# bone_capes.net
KiCad netlist of a schematic drawn in Altium Designer
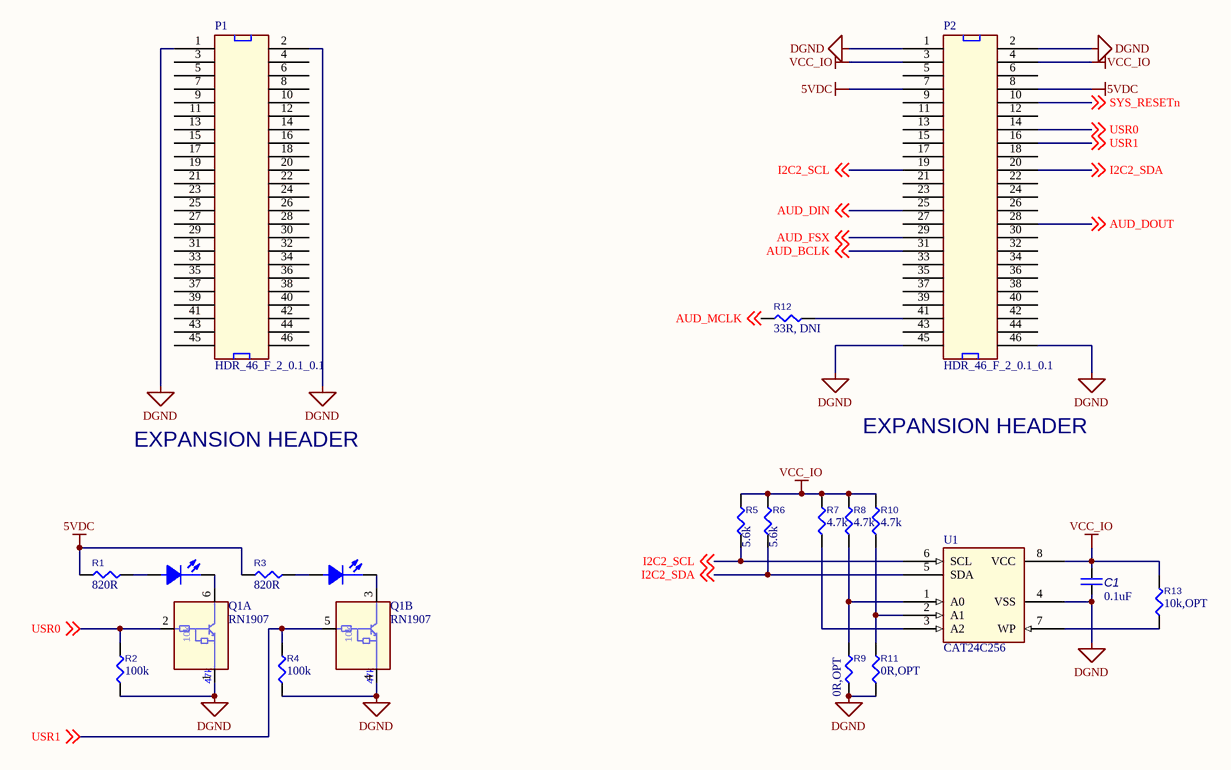
[diagram p0: bone_capes.SchDoc]

(export (version "E")
  (design (tool "Eeschema 10.0.6"))
  (components
    (comp (ref "C1")
      (value "0.1uF")
      (footprint "CC1608-0603")
      (description "C0603")
      (libsource (lib "usomiq-audio") (part "C0603"))
    )
    (comp (ref "D1")
      (value "LED0805")
      (footprint "LED0805")
      (description "LED 0805")
      (libsource (lib "am335x-base") (part "LED0805"))
    )
    (comp (ref "D2")
      (value "LED0805")
      (footprint "LED0805")
      (description "LED 0805")
      (libsource (lib "am335x-base") (part "LED0805"))
    )
    (comp (ref "P1")
      (value "HDR_46_F_2_0.1_0.1")
      (footprint "DIP46")
      (description "NN HEADER FMAL 46PS.1\" DL GOLD")
      (fields (field (name "MFR") "major league electronics"))
      (libsource (lib "usomiq-audio") (part "HDR_46_F_2_0.1_0.1"))
    )
    (comp (ref "P2")
      (value "HDR_46_F_2_0.1_0.1")
      (footprint "DIP46")
      (description "NN HEADER FMAL 46PS.1\" DL GOLD")
      (fields (field (name "MFR") "major league electronics"))
      (libsource (lib "usomiq-audio") (part "HDR_46_F_2_0.1_0.1"))
    )
    (comp (ref "Q1")
      (value "RN1907")
      (footprint "SOT363-6L")
      (description "Transistor Silicon NPN")
      (fields (field (name "MFR") "Panasonic"))
      (libsource (lib "am335x-base") (part "RN1907"))
    )
    (comp (ref "R1")
      (value "820R")
      (footprint "RESC1608X55N")
      (description "R0603")
      (libsource (lib "am335x-base") (part "R0603"))
    )
    (comp (ref "R2")
      (value "100k")
      (footprint "RESC1608X55N")
      (description "R0603")
      (libsource (lib "am335x-base") (part "R0603"))
    )
    (comp (ref "R3")
      (value "820R")
      (footprint "RESC1608X55N")
      (description "R0603")
      (libsource (lib "am335x-base") (part "R0603"))
    )
    (comp (ref "R4")
      (value "100k")
      (footprint "RESC1608X55N")
      (description "R0603")
      (libsource (lib "am335x-base") (part "R0603"))
    )
    (comp (ref "R5")
      (value "5.6k")
      (footprint "RESC1608X55N")
      (description "R0603")
      (libsource (lib "usomiq-audio") (part "R0603"))
    )
    (comp (ref "R6")
      (value "5.6k")
      (footprint "RESC1608X55N")
      (description "R0603")
      (libsource (lib "usomiq-audio") (part "R0603"))
    )
    (comp (ref "R7")
      (value "4.7k")
      (footprint "RESC1608X55N")
      (description "R0603")
      (libsource (lib "usomiq-audio") (part "R0603"))
    )
    (comp (ref "R8")
      (value "4.7k")
      (footprint "RESC1608X55N")
      (description "R0603")
      (libsource (lib "usomiq-audio") (part "R0603"))
    )
    (comp (ref "R9")
      (value "0R,OPT")
      (footprint "RESC1608X55N")
      (description "R0603")
      (libsource (lib "usomiq-audio") (part "R0603"))
    )
    (comp (ref "R10")
      (value "4.7k")
      (footprint "RESC1608X55N")
      (description "R0603")
      (libsource (lib "usomiq-audio") (part "R0603"))
    )
    (comp (ref "R11")
      (value "0R,OPT")
      (footprint "RESC1608X55N")
      (description "R0603")
      (libsource (lib "usomiq-audio") (part "R0603"))
    )
    (comp (ref "R12")
      (value "33R, DNI")
      (footprint "RESC1608X55N")
      (description "R0603")
      (libsource (lib "usomiq-audio") (part "R0603"))
    )
    (comp (ref "R13")
      (value "10k,OPT")
      (footprint "RESC1608X55N")
      (description "R0603")
      (libsource (lib "usomiq-audio") (part "R0603"))
    )
    (comp (ref "U1")
      (value "CAT24C256")
      (footprint "SOIC127P600X173-8L")
      (description "256 kb I2C CMOS Serial  EEPROM")
      (fields (field (name "MANUFACTURER") "ON Semiconductor"))
      (libsource (lib "usomiq-audio") (part "CAT24C256"))
    )
  )
  (nets
    (net (code "1") (name "5VDC") (class "Default")
      (node (ref "P2") (pin "7") (pinfunction "4_7") (pintype "passive"))
      (node (ref "P2") (pin "8") (pinfunction "29_8") (pintype "passive"))
      (node (ref "R1") (pin "2") (pinfunction "2_2") (pintype "passive"))
      (node (ref "R3") (pin "2") (pinfunction "2_2") (pintype "passive"))
    )
    (net (code "2") (name "AUD_BCLK") (class "Default")
      (node (ref "P2") (pin "31") (pinfunction "16_31") (pintype "passive"))
    )
    (net (code "3") (name "AUD_DIN") (class "Default")
      (node (ref "P2") (pin "25") (pinfunction "13_25") (pintype "passive"))
    )
    (net (code "4") (name "AUD_DOUT") (class "Default")
      (node (ref "P2") (pin "28") (pinfunction "39_28") (pintype "passive"))
    )
    (net (code "5") (name "AUD_FSX") (class "Default")
      (node (ref "P2") (pin "29") (pinfunction "15_29") (pintype "passive"))
    )
    (net (code "6") (name "AUD_MCLK") (class "Default")
      (node (ref "R12") (pin "1") (pinfunction "1_1") (pintype "passive"))
    )
    (net (code "7") (name "DGND") (class "Default")
      (node (ref "C1") (pin "2") (pinfunction "2_2") (pintype "passive"))
      (node (ref "P1") (pin "1") (pinfunction "1_1") (pintype "passive"))
      (node (ref "P1") (pin "2") (pinfunction "26_2") (pintype "passive"))
      (node (ref "P2") (pin "1") (pinfunction "1_1") (pintype "passive"))
      (node (ref "P2") (pin "2") (pinfunction "26_2") (pintype "passive"))
      (node (ref "P2") (pin "45") (pinfunction "23_45") (pintype "passive"))
      (node (ref "P2") (pin "46") (pinfunction "48_46") (pintype "passive"))
      (node (ref "Q1") (pin "1") (pinfunction "4_1") (pintype "passive"))
      (node (ref "Q1") (pin "4") (pinfunction "4_4") (pintype "passive"))
      (node (ref "R11") (pin "1") (pinfunction "1_1") (pintype "passive"))
      (node (ref "R2") (pin "1") (pinfunction "1_1") (pintype "passive"))
      (node (ref "R4") (pin "1") (pinfunction "1_1") (pintype "passive"))
      (node (ref "R9") (pin "1") (pinfunction "1_1") (pintype "passive"))
      (node (ref "U1") (pin "4") (pinfunction "VSS_4") (pintype "passive"))
    )
    (net (code "8") (name "I2C2_SCL") (class "Default")
      (node (ref "P2") (pin "19") (pinfunction "10_19") (pintype "passive"))
      (node (ref "R5") (pin "1") (pinfunction "1_1") (pintype "passive"))
      (node (ref "U1") (pin "6") (pinfunction "SCL_6") (pintype "input"))
    )
    (net (code "9") (name "I2C2_SDA") (class "Default")
      (node (ref "P2") (pin "20") (pinfunction "35_20") (pintype "passive"))
      (node (ref "R6") (pin "1") (pinfunction "1_1") (pintype "passive"))
      (node (ref "U1") (pin "5") (pinfunction "SDA_5") (pintype "passive"))
    )
    (net (code "10") (name "Net-(D1-A)") (class "Default")
      (node (ref "D1") (pin "1") (pinfunction "A_1") (pintype "passive"))
      (node (ref "R1") (pin "1") (pinfunction "1_1") (pintype "passive"))
    )
    (net (code "11") (name "Net-(D1-C)") (class "Default")
      (node (ref "D1") (pin "2") (pinfunction "C_2") (pintype "passive"))
      (node (ref "Q1") (pin "6") (pinfunction "3_6") (pintype "passive"))
    )
    (net (code "12") (name "Net-(D2-A)") (class "Default")
      (node (ref "D2") (pin "1") (pinfunction "A_1") (pintype "passive"))
      (node (ref "R3") (pin "1") (pinfunction "1_1") (pintype "passive"))
    )
    (net (code "13") (name "Net-(D2-C)") (class "Default")
      (node (ref "D2") (pin "2") (pinfunction "C_2") (pintype "passive"))
      (node (ref "Q1") (pin "3") (pinfunction "3_3") (pintype "passive"))
    )
    (net (code "14") (name "Net-(P2-21)") (class "Default")
      (node (ref "P2") (pin "41") (pinfunction "21_41") (pintype "passive"))
      (node (ref "R12") (pin "2") (pinfunction "2_2") (pintype "passive"))
    )
    (net (code "15") (name "Net-(U1-A0)") (class "Default")
      (node (ref "R8") (pin "1") (pinfunction "1_1") (pintype "passive"))
      (node (ref "R9") (pin "2") (pinfunction "2_2") (pintype "passive"))
      (node (ref "U1") (pin "1") (pinfunction "A0_1") (pintype "input"))
    )
    (net (code "16") (name "Net-(U1-A1)") (class "Default")
      (node (ref "R10") (pin "1") (pinfunction "1_1") (pintype "passive"))
      (node (ref "R11") (pin "2") (pinfunction "2_2") (pintype "passive"))
      (node (ref "U1") (pin "2") (pinfunction "A1_2") (pintype "input"))
    )
    (net (code "17") (name "Net-(U1-A2)") (class "Default")
      (node (ref "R7") (pin "1") (pinfunction "1_1") (pintype "passive"))
      (node (ref "U1") (pin "3") (pinfunction "A2_3") (pintype "input"))
    )
    (net (code "18") (name "Net-(U1-WP)") (class "Default")
      (node (ref "R13") (pin "1") (pinfunction "1_1") (pintype "passive"))
      (node (ref "U1") (pin "7") (pinfunction "WP_7") (pintype "input"))
    )
    (net (code "19") (name "SYS_RESETn") (class "Default")
      (node (ref "P2") (pin "10") (pinfunction "30_10") (pintype "passive"))
    )
    (net (code "20") (name "USR0") (class "Default")
      (node (ref "P2") (pin "14") (pinfunction "32_14") (pintype "passive"))
      (node (ref "Q1") (pin "2") (pinfunction "5_2") (pintype "passive"))
      (node (ref "R2") (pin "2") (pinfunction "2_2") (pintype "passive"))
    )
    (net (code "21") (name "USR1") (class "Default")
      (node (ref "P2") (pin "16") (pinfunction "33_16") (pintype "passive"))
      (node (ref "Q1") (pin "5") (pinfunction "5_5") (pintype "passive"))
      (node (ref "R4") (pin "2") (pinfunction "2_2") (pintype "passive"))
    )
    (net (code "22") (name "VCC_IO") (class "Default")
      (node (ref "C1") (pin "1") (pinfunction "1_1") (pintype "passive"))
      (node (ref "P2") (pin "3") (pinfunction "2_3") (pintype "passive"))
      (node (ref "P2") (pin "4") (pinfunction "27_4") (pintype "passive"))
      (node (ref "R10") (pin "2") (pinfunction "2_2") (pintype "passive"))
      (node (ref "R13") (pin "2") (pinfunction "2_2") (pintype "passive"))
      (node (ref "R5") (pin "2") (pinfunction "2_2") (pintype "passive"))
      (node (ref "R6") (pin "2") (pinfunction "2_2") (pintype "passive"))
      (node (ref "R7") (pin "2") (pinfunction "2_2") (pintype "passive"))
      (node (ref "R8") (pin "2") (pinfunction "2_2") (pintype "passive"))
      (node (ref "U1") (pin "8") (pinfunction "VCC_8") (pintype "passive"))
    )
    (net (code "23") (name "unconnected-(P1-2-Pad3)") (class "Default")
      (node (ref "P1") (pin "3") (pinfunction "2_3") (pintype "passive"))
    )
    (net (code "24") (name "unconnected-(P1-3-Pad5)") (class "Default")
      (node (ref "P1") (pin "5") (pinfunction "3_5") (pintype "passive"))
    )
    (net (code "25") (name "unconnected-(P1-4-Pad7)") (class "Default")
      (node (ref "P1") (pin "7") (pinfunction "4_7") (pintype "passive"))
    )
    (net (code "26") (name "unconnected-(P1-5-Pad9)") (class "Default")
      (node (ref "P1") (pin "9") (pinfunction "5_9") (pintype "passive"))
    )
    (net (code "27") (name "unconnected-(P1-6-Pad11)") (class "Default")
      (node (ref "P1") (pin "11") (pinfunction "6_11") (pintype "passive"))
    )
    (net (code "28") (name "unconnected-(P1-7-Pad13)") (class "Default")
      (node (ref "P1") (pin "13") (pinfunction "7_13") (pintype "passive"))
    )
    (net (code "29") (name "unconnected-(P1-8-Pad15)") (class "Default")
      (node (ref "P1") (pin "15") (pinfunction "8_15") (pintype "passive"))
    )
    (net (code "30") (name "unconnected-(P1-9-Pad17)") (class "Default")
      (node (ref "P1") (pin "17") (pinfunction "9_17") (pintype "passive"))
    )
    (net (code "31") (name "unconnected-(P1-10-Pad19)") (class "Default")
      (node (ref "P1") (pin "19") (pinfunction "10_19") (pintype "passive"))
    )
    (net (code "32") (name "unconnected-(P1-11-Pad21)") (class "Default")
      (node (ref "P1") (pin "21") (pinfunction "11_21") (pintype "passive"))
    )
    (net (code "33") (name "unconnected-(P1-12-Pad23)") (class "Default")
      (node (ref "P1") (pin "23") (pinfunction "12_23") (pintype "passive"))
    )
    (net (code "34") (name "unconnected-(P1-13-Pad25)") (class "Default")
      (node (ref "P1") (pin "25") (pinfunction "13_25") (pintype "passive"))
    )
    (net (code "35") (name "unconnected-(P1-14-Pad27)") (class "Default")
      (node (ref "P1") (pin "27") (pinfunction "14_27") (pintype "passive"))
    )
    (net (code "36") (name "unconnected-(P1-15-Pad29)") (class "Default")
      (node (ref "P1") (pin "29") (pinfunction "15_29") (pintype "passive"))
    )
    (net (code "37") (name "unconnected-(P1-16-Pad31)") (class "Default")
      (node (ref "P1") (pin "31") (pinfunction "16_31") (pintype "passive"))
    )
    (net (code "38") (name "unconnected-(P1-17-Pad33)") (class "Default")
      (node (ref "P1") (pin "33") (pinfunction "17_33") (pintype "passive"))
    )
    (net (code "39") (name "unconnected-(P1-18-Pad35)") (class "Default")
      (node (ref "P1") (pin "35") (pinfunction "18_35") (pintype "passive"))
    )
    (net (code "40") (name "unconnected-(P1-19-Pad37)") (class "Default")
      (node (ref "P1") (pin "37") (pinfunction "19_37") (pintype "passive"))
    )
    (net (code "41") (name "unconnected-(P1-20-Pad39)") (class "Default")
      (node (ref "P1") (pin "39") (pinfunction "20_39") (pintype "passive"))
    )
    (net (code "42") (name "unconnected-(P1-21-Pad41)") (class "Default")
      (node (ref "P1") (pin "41") (pinfunction "21_41") (pintype "passive"))
    )
    (net (code "43") (name "unconnected-(P1-22-Pad43)") (class "Default")
      (node (ref "P1") (pin "43") (pinfunction "22_43") (pintype "passive"))
    )
    (net (code "44") (name "unconnected-(P1-23-Pad45)") (class "Default")
      (node (ref "P1") (pin "45") (pinfunction "23_45") (pintype "passive"))
    )
    (net (code "45") (name "unconnected-(P1-27-Pad4)") (class "Default")
      (node (ref "P1") (pin "4") (pinfunction "27_4") (pintype "passive"))
    )
    (net (code "46") (name "unconnected-(P1-28-Pad6)") (class "Default")
      (node (ref "P1") (pin "6") (pinfunction "28_6") (pintype "passive"))
    )
    (net (code "47") (name "unconnected-(P1-29-Pad8)") (class "Default")
      (node (ref "P1") (pin "8") (pinfunction "29_8") (pintype "passive"))
    )
    (net (code "48") (name "unconnected-(P1-30-Pad10)") (class "Default")
      (node (ref "P1") (pin "10") (pinfunction "30_10") (pintype "passive"))
    )
    (net (code "49") (name "unconnected-(P1-31-Pad12)") (class "Default")
      (node (ref "P1") (pin "12") (pinfunction "31_12") (pintype "passive"))
    )
    (net (code "50") (name "unconnected-(P1-32-Pad14)") (class "Default")
      (node (ref "P1") (pin "14") (pinfunction "32_14") (pintype "passive"))
    )
    (net (code "51") (name "unconnected-(P1-33-Pad16)") (class "Default")
      (node (ref "P1") (pin "16") (pinfunction "33_16") (pintype "passive"))
    )
    (net (code "52") (name "unconnected-(P1-34-Pad18)") (class "Default")
      (node (ref "P1") (pin "18") (pinfunction "34_18") (pintype "passive"))
    )
    (net (code "53") (name "unconnected-(P1-35-Pad20)") (class "Default")
      (node (ref "P1") (pin "20") (pinfunction "35_20") (pintype "passive"))
    )
    (net (code "54") (name "unconnected-(P1-36-Pad22)") (class "Default")
      (node (ref "P1") (pin "22") (pinfunction "36_22") (pintype "passive"))
    )
    (net (code "55") (name "unconnected-(P1-37-Pad24)") (class "Default")
      (node (ref "P1") (pin "24") (pinfunction "37_24") (pintype "passive"))
    )
    (net (code "56") (name "unconnected-(P1-38-Pad26)") (class "Default")
      (node (ref "P1") (pin "26") (pinfunction "38_26") (pintype "passive"))
    )
    (net (code "57") (name "unconnected-(P1-39-Pad28)") (class "Default")
      (node (ref "P1") (pin "28") (pinfunction "39_28") (pintype "passive"))
    )
    (net (code "58") (name "unconnected-(P1-40-Pad30)") (class "Default")
      (node (ref "P1") (pin "30") (pinfunction "40_30") (pintype "passive"))
    )
    (net (code "59") (name "unconnected-(P1-41-Pad32)") (class "Default")
      (node (ref "P1") (pin "32") (pinfunction "41_32") (pintype "passive"))
    )
    (net (code "60") (name "unconnected-(P1-42-Pad34)") (class "Default")
      (node (ref "P1") (pin "34") (pinfunction "42_34") (pintype "passive"))
    )
    (net (code "61") (name "unconnected-(P1-43-Pad36)") (class "Default")
      (node (ref "P1") (pin "36") (pinfunction "43_36") (pintype "passive"))
    )
    (net (code "62") (name "unconnected-(P1-44-Pad38)") (class "Default")
      (node (ref "P1") (pin "38") (pinfunction "44_38") (pintype "passive"))
    )
    (net (code "63") (name "unconnected-(P1-45-Pad40)") (class "Default")
      (node (ref "P1") (pin "40") (pinfunction "45_40") (pintype "passive"))
    )
    (net (code "64") (name "unconnected-(P1-46-Pad42)") (class "Default")
      (node (ref "P1") (pin "42") (pinfunction "46_42") (pintype "passive"))
    )
    (net (code "65") (name "unconnected-(P1-47-Pad44)") (class "Default")
      (node (ref "P1") (pin "44") (pinfunction "47_44") (pintype "passive"))
    )
    (net (code "66") (name "unconnected-(P1-48-Pad46)") (class "Default")
      (node (ref "P1") (pin "46") (pinfunction "48_46") (pintype "passive"))
    )
    (net (code "67") (name "unconnected-(P2-3-Pad5)") (class "Default")
      (node (ref "P2") (pin "5") (pinfunction "3_5") (pintype "passive"))
    )
    (net (code "68") (name "unconnected-(P2-5-Pad9)") (class "Default")
      (node (ref "P2") (pin "9") (pinfunction "5_9") (pintype "passive"))
    )
    (net (code "69") (name "unconnected-(P2-6-Pad11)") (class "Default")
      (node (ref "P2") (pin "11") (pinfunction "6_11") (pintype "passive"))
    )
    (net (code "70") (name "unconnected-(P2-7-Pad13)") (class "Default")
      (node (ref "P2") (pin "13") (pinfunction "7_13") (pintype "passive"))
    )
    (net (code "71") (name "unconnected-(P2-8-Pad15)") (class "Default")
      (node (ref "P2") (pin "15") (pinfunction "8_15") (pintype "passive"))
    )
    (net (code "72") (name "unconnected-(P2-9-Pad17)") (class "Default")
      (node (ref "P2") (pin "17") (pinfunction "9_17") (pintype "passive"))
    )
    (net (code "73") (name "unconnected-(P2-11-Pad21)") (class "Default")
      (node (ref "P2") (pin "21") (pinfunction "11_21") (pintype "passive"))
    )
    (net (code "74") (name "unconnected-(P2-12-Pad23)") (class "Default")
      (node (ref "P2") (pin "23") (pinfunction "12_23") (pintype "passive"))
    )
    (net (code "75") (name "unconnected-(P2-14-Pad27)") (class "Default")
      (node (ref "P2") (pin "27") (pinfunction "14_27") (pintype "passive"))
    )
    (net (code "76") (name "unconnected-(P2-17-Pad33)") (class "Default")
      (node (ref "P2") (pin "33") (pinfunction "17_33") (pintype "passive"))
    )
    (net (code "77") (name "unconnected-(P2-18-Pad35)") (class "Default")
      (node (ref "P2") (pin "35") (pinfunction "18_35") (pintype "passive"))
    )
    (net (code "78") (name "unconnected-(P2-19-Pad37)") (class "Default")
      (node (ref "P2") (pin "37") (pinfunction "19_37") (pintype "passive"))
    )
    (net (code "79") (name "unconnected-(P2-20-Pad39)") (class "Default")
      (node (ref "P2") (pin "39") (pinfunction "20_39") (pintype "passive"))
    )
    (net (code "80") (name "unconnected-(P2-22-Pad43)") (class "Default")
      (node (ref "P2") (pin "43") (pinfunction "22_43") (pintype "passive"))
    )
    (net (code "81") (name "unconnected-(P2-28-Pad6)") (class "Default")
      (node (ref "P2") (pin "6") (pinfunction "28_6") (pintype "passive"))
    )
    (net (code "82") (name "unconnected-(P2-31-Pad12)") (class "Default")
      (node (ref "P2") (pin "12") (pinfunction "31_12") (pintype "passive"))
    )
    (net (code "83") (name "unconnected-(P2-34-Pad18)") (class "Default")
      (node (ref "P2") (pin "18") (pinfunction "34_18") (pintype "passive"))
    )
    (net (code "84") (name "unconnected-(P2-36-Pad22)") (class "Default")
      (node (ref "P2") (pin "22") (pinfunction "36_22") (pintype "passive"))
    )
    (net (code "85") (name "unconnected-(P2-37-Pad24)") (class "Default")
      (node (ref "P2") (pin "24") (pinfunction "37_24") (pintype "passive"))
    )
    (net (code "86") (name "unconnected-(P2-38-Pad26)") (class "Default")
      (node (ref "P2") (pin "26") (pinfunction "38_26") (pintype "passive"))
    )
    (net (code "87") (name "unconnected-(P2-40-Pad30)") (class "Default")
      (node (ref "P2") (pin "30") (pinfunction "40_30") (pintype "passive"))
    )
    (net (code "88") (name "unconnected-(P2-41-Pad32)") (class "Default")
      (node (ref "P2") (pin "32") (pinfunction "41_32") (pintype "passive"))
    )
    (net (code "89") (name "unconnected-(P2-42-Pad34)") (class "Default")
      (node (ref "P2") (pin "34") (pinfunction "42_34") (pintype "passive"))
    )
    (net (code "90") (name "unconnected-(P2-43-Pad36)") (class "Default")
      (node (ref "P2") (pin "36") (pinfunction "43_36") (pintype "passive"))
    )
    (net (code "91") (name "unconnected-(P2-44-Pad38)") (class "Default")
      (node (ref "P2") (pin "38") (pinfunction "44_38") (pintype "passive"))
    )
    (net (code "92") (name "unconnected-(P2-45-Pad40)") (class "Default")
      (node (ref "P2") (pin "40") (pinfunction "45_40") (pintype "passive"))
    )
    (net (code "93") (name "unconnected-(P2-46-Pad42)") (class "Default")
      (node (ref "P2") (pin "42") (pinfunction "46_42") (pintype "passive"))
    )
    (net (code "94") (name "unconnected-(P2-47-Pad44)") (class "Default")
      (node (ref "P2") (pin "44") (pinfunction "47_44") (pintype "passive"))
    )
  )
)
